# voltage_level_translators_schematic.net
KiCad netlist of a schematic drawn in Altium Designer
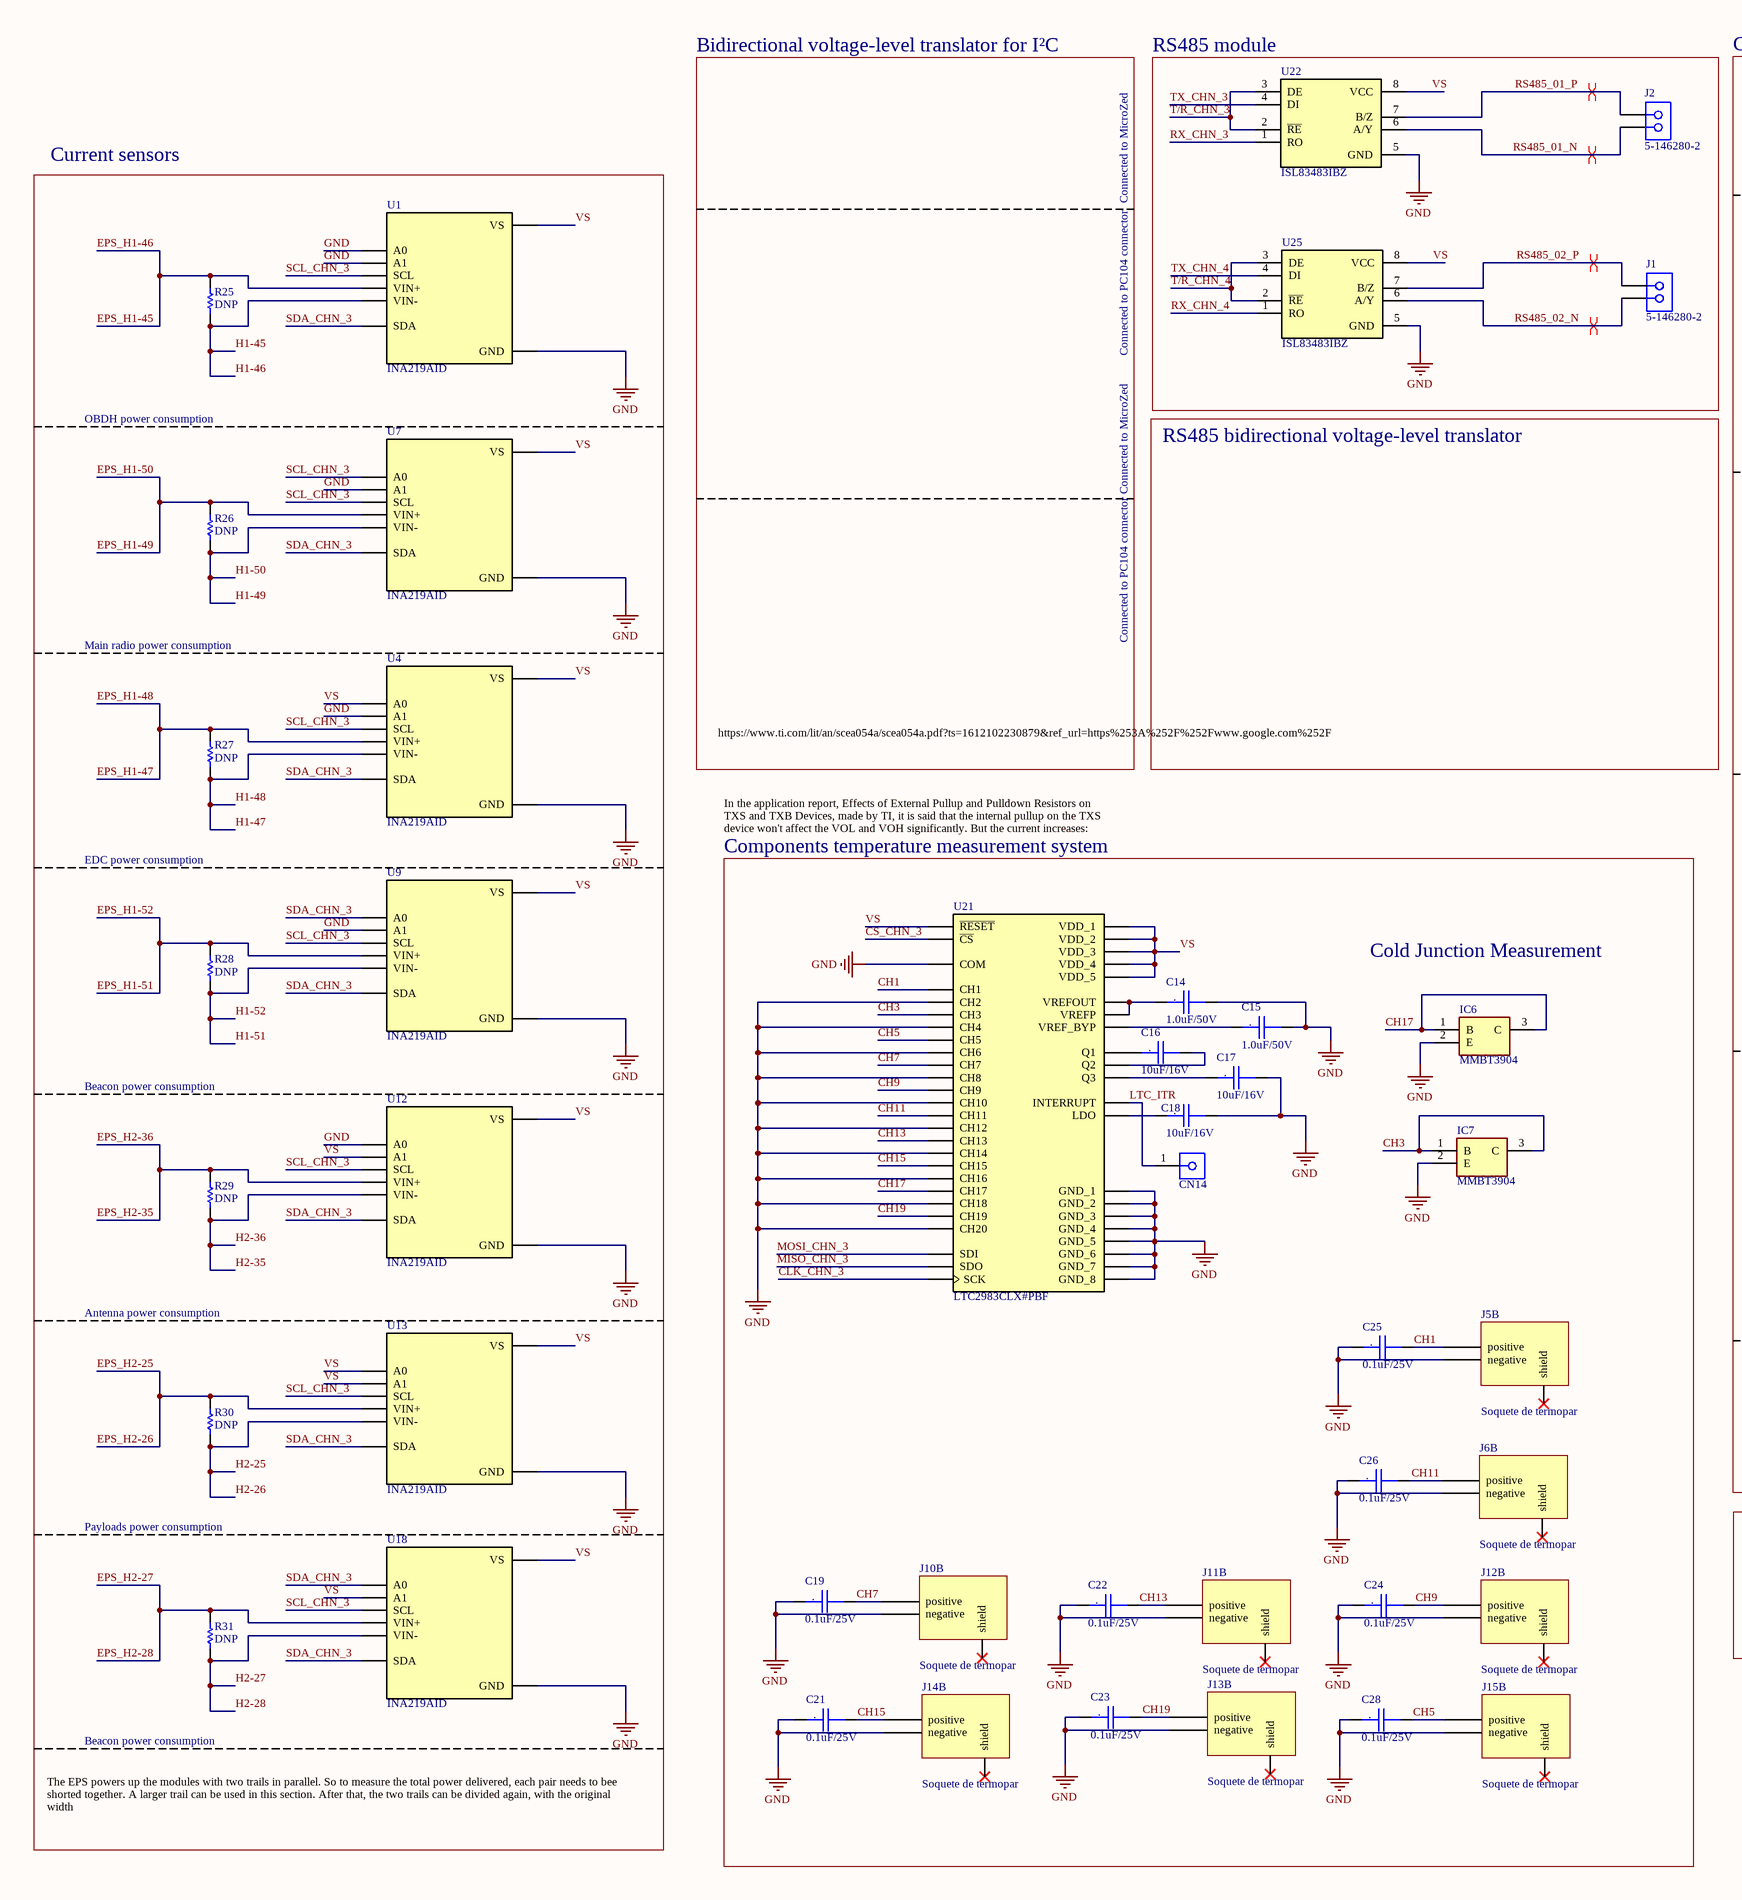
[diagram p0: voltage_level_translators_schematic.SchDoc, left]
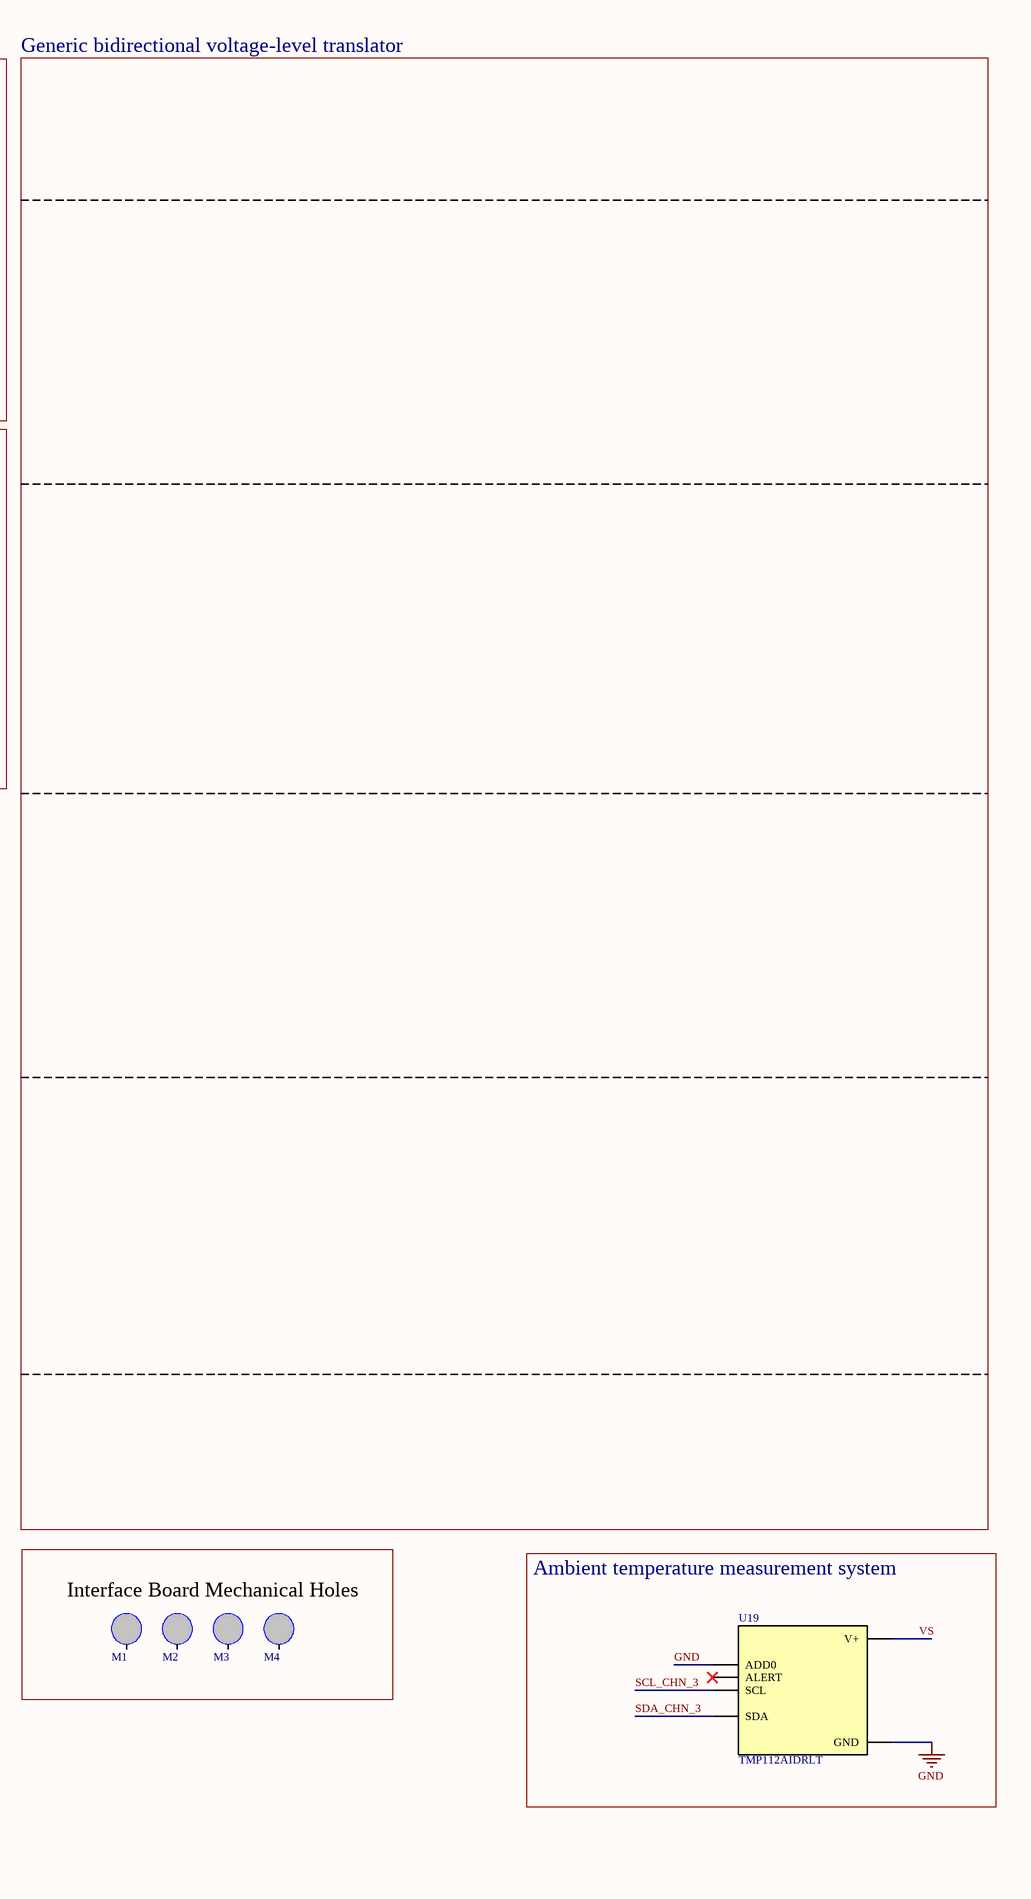
[diagram p1: voltage_level_translators_schematic.SchDoc, right]

(export (version "E")
  (design (tool "Eeschema 10.0.6"))
  (components
    (comp (ref "C14")
      (value "1.0uF/50V")
      (footprint "CC0805")
      (description "CAP CER 1.0uF 50V 10% X7R 0805")
      (fields (field (name "MANUFACTURER PART NUMBER") "C0805X105K5RACAUTO"))
      (libsource (lib "flatsat_platform_2") (part "Cap_Cer_X7R_1.0uF_50V_0805"))
    )
    (comp (ref "C15")
      (value "1.0uF/50V")
      (footprint "CC0805")
      (description "CAP CER 1.0uF 50V 10% X7R 0805")
      (fields (field (name "MANUFACTURER PART NUMBER") "C0805X105K5RACAUTO"))
      (libsource (lib "flatsat_platform_2") (part "Cap_Cer_X7R_1.0uF_50V_0805"))
    )
    (comp (ref "C16")
      (value "10uF/16V")
      (footprint "CC1210")
      (description "CAP CER 10uF 16V 10% X7R 1210")
      (fields (field (name "MANUFACTURER PART NUMBER") "C1210C106K4RACTU"))
      (libsource (lib "flatsat_platform_2") (part "Cap_Cer_X7R_10uF_16V_1210"))
    )
    (comp (ref "C17")
      (value "10uF/16V")
      (footprint "CC1210")
      (description "CAP CER 10uF 16V 10% X7R 1210")
      (fields (field (name "MANUFACTURER PART NUMBER") "C1210C106K4RACTU"))
      (libsource (lib "flatsat_platform_2") (part "Cap_Cer_X7R_10uF_16V_1210"))
    )
    (comp (ref "C18")
      (value "10uF/16V")
      (footprint "CC1210")
      (description "CAP CER 10uF 16V 10% X7R 1210")
      (fields (field (name "MANUFACTURER PART NUMBER") "C1210C106K4RACTU"))
      (libsource (lib "flatsat_platform_2") (part "Cap_Cer_X7R_10uF_16V_1210"))
    )
    (comp (ref "C19")
      (value "0.1uF/25V")
      (footprint "CC0805")
      (description "CAP CER 0.1uF 25V 10% X7R 0805")
      (fields (field (name "MANUFACTURER PART NUMBER") "CC0805KRX7R8BB104"))
      (libsource (lib "flatsat_platform_2") (part "Cap_Cer_X7R_0.1uF_25V_0805"))
    )
    (comp (ref "C21")
      (value "0.1uF/25V")
      (footprint "CC0805")
      (description "CAP CER 0.1uF 25V 10% X7R 0805")
      (fields (field (name "MANUFACTURER PART NUMBER") "CC0805KRX7R8BB104"))
      (libsource (lib "flatsat_platform_2") (part "Cap_Cer_X7R_0.1uF_25V_0805"))
    )
    (comp (ref "C22")
      (value "0.1uF/25V")
      (footprint "CC0805")
      (description "CAP CER 0.1uF 25V 10% X7R 0805")
      (fields (field (name "MANUFACTURER PART NUMBER") "CC0805KRX7R8BB104"))
      (libsource (lib "flatsat_platform_2") (part "Cap_Cer_X7R_0.1uF_25V_0805"))
    )
    (comp (ref "C23")
      (value "0.1uF/25V")
      (footprint "CC0805")
      (description "CAP CER 0.1uF 25V 10% X7R 0805")
      (fields (field (name "MANUFACTURER PART NUMBER") "CC0805KRX7R8BB104"))
      (libsource (lib "flatsat_platform_2") (part "Cap_Cer_X7R_0.1uF_25V_0805"))
    )
    (comp (ref "C24")
      (value "0.1uF/25V")
      (footprint "CC0805")
      (description "CAP CER 0.1uF 25V 10% X7R 0805")
      (fields (field (name "MANUFACTURER PART NUMBER") "CC0805KRX7R8BB104"))
      (libsource (lib "flatsat_platform_2") (part "Cap_Cer_X7R_0.1uF_25V_0805"))
    )
    (comp (ref "C25")
      (value "0.1uF/25V")
      (footprint "CC0805")
      (description "CAP CER 0.1uF 25V 10% X7R 0805")
      (fields (field (name "MANUFACTURER PART NUMBER") "CC0805KRX7R8BB104"))
      (libsource (lib "flatsat_platform_2") (part "Cap_Cer_X7R_0.1uF_25V_0805"))
    )
    (comp (ref "C26")
      (value "0.1uF/25V")
      (footprint "CC0805")
      (description "CAP CER 0.1uF 25V 10% X7R 0805")
      (fields (field (name "MANUFACTURER PART NUMBER") "CC0805KRX7R8BB104"))
      (libsource (lib "flatsat_platform_2") (part "Cap_Cer_X7R_0.1uF_25V_0805"))
    )
    (comp (ref "C28")
      (value "0.1uF/25V")
      (footprint "CC0805")
      (description "CAP CER 0.1uF 25V 10% X7R 0805")
      (fields (field (name "MANUFACTURER PART NUMBER") "CC0805KRX7R8BB104"))
      (libsource (lib "flatsat_platform_2") (part "Cap_Cer_X7R_0.1uF_25V_0805"))
    )
    (comp (ref "CN14")
      (value "TSW-101-05-T-S")
      (footprint "PIN BAR 1 2.54mm 180 GRAUS - Hide")
      (description "CONN HEADER 1POS .100\" SNGL TIN")
      (fields (field (name "MANUFACTURER") "Samtec Inc"))
      (libsource (lib "flatsat_platform_2") (part "TSW-101-05-T-S"))
    )
    (comp (ref "IC6")
      (value "MMBT3904")
      (footprint "SamacSys:SOT95P240X120-3N")
      (description "Integrated Circuit")
      (fields (field (name "MOUSER PART NUMBER") "637-MMBT3904"))
      (libsource (lib "*") (part "MMBT3904"))
    )
    (comp (ref "IC7")
      (value "MMBT3904")
      (footprint "SamacSys:SOT95P240X120-3N")
      (description "Integrated Circuit")
      (fields (field (name "MOUSER PART NUMBER") "637-MMBT3904"))
      (libsource (lib "*") (part "MMBT3904"))
    )
    (comp (ref "J1")
      (value "5-146280-2")
      (footprint "PIN BAR 2 2.54mm 180 GRAUS")
      (description "02 MODII HDR SRST B/A .100CL")
      (fields (field (name "MF") "TE Connectivity"))
      (libsource (lib "flatsat_platform_2") (part "5-146280-2"))
    )
    (comp (ref "J2")
      (value "5-146280-2")
      (footprint "PIN BAR 2 2.54mm 180 GRAUS")
      (description "02 MODII HDR SRST B/A .100CL")
      (fields (field (name "MF") "TE Connectivity"))
      (libsource (lib "flatsat_platform_2") (part "5-146280-2"))
    )
    (comp (ref "J5")
      (value "Soquete de termopar")
      (footprint "PCC-SMP-V-K")
      (description "Soquete de termopar especial PCCS para placa de circuito em série")
      (libsource (lib "Thermocouple_connector") (part "PCC-SMP-V-K"))
    )
    (comp (ref "J6")
      (value "Soquete de termopar")
      (footprint "PCC-SMP-V-K")
      (description "Soquete de termopar especial PCCS para placa de circuito em série")
      (libsource (lib "Thermocouple_connector") (part "PCC-SMP-V-K"))
    )
    (comp (ref "J10")
      (value "Soquete de termopar")
      (footprint "PCC-SMP-V-K")
      (description "Soquete de termopar especial PCCS para placa de circuito em série")
      (libsource (lib "Thermocouple_connector") (part "PCC-SMP-V-K"))
    )
    (comp (ref "J11")
      (value "Soquete de termopar")
      (footprint "PCC-SMP-V-K")
      (description "Soquete de termopar especial PCCS para placa de circuito em série")
      (libsource (lib "Thermocouple_connector") (part "PCC-SMP-V-K"))
    )
    (comp (ref "J12")
      (value "Soquete de termopar")
      (footprint "PCC-SMP-V-K")
      (description "Soquete de termopar especial PCCS para placa de circuito em série")
      (libsource (lib "Thermocouple_connector") (part "PCC-SMP-V-K"))
    )
    (comp (ref "J13")
      (value "Soquete de termopar")
      (footprint "PCC-SMP-V-K")
      (description "Soquete de termopar especial PCCS para placa de circuito em série")
      (libsource (lib "Thermocouple_connector") (part "PCC-SMP-V-K"))
    )
    (comp (ref "J14")
      (value "Soquete de termopar")
      (footprint "PCC-SMP-V-K")
      (description "Soquete de termopar especial PCCS para placa de circuito em série")
      (libsource (lib "Thermocouple_connector") (part "PCC-SMP-V-K"))
    )
    (comp (ref "J15")
      (value "Soquete de termopar")
      (footprint "PCC-SMP-V-K")
      (description "Soquete de termopar especial PCCS para placa de circuito em série")
      (libsource (lib "Thermocouple_connector") (part "PCC-SMP-V-K"))
    )
    (comp (ref "M1")
      (value "IB Mechanical Hole")
      (footprint "M3 hole (5.5mm pad)")
      (description "Mechanical Hole for FloripaSat-2 interface boards")
      (libsource (lib "iip") (part "IB Mechanical Hole"))
    )
    (comp (ref "M2")
      (value "IB Mechanical Hole")
      (footprint "M3 hole (5.5mm pad)")
      (description "Mechanical Hole for FloripaSat-2 interface boards")
      (libsource (lib "iip") (part "IB Mechanical Hole"))
    )
    (comp (ref "M3")
      (value "IB Mechanical Hole")
      (footprint "M3 hole (5.5mm pad)")
      (description "Mechanical Hole for FloripaSat-2 interface boards")
      (libsource (lib "iip") (part "IB Mechanical Hole"))
    )
    (comp (ref "M4")
      (value "IB Mechanical Hole")
      (footprint "M3 hole (5.5mm pad)")
      (description "Mechanical Hole for FloripaSat-2 interface boards")
      (libsource (lib "iip") (part "IB Mechanical Hole"))
    )
    (comp (ref "R25")
      (value "DNP")
      (footprint "0805")
      (description "RES DNP 0805")
      (fields (field (name "MANUFACTURER PART NUMBER") "UR73V2ATTD47L0F"))
      (libsource (lib "flatsat_platform_2") (part "RDNP_0805"))
    )
    (comp (ref "R26")
      (value "DNP")
      (footprint "0805")
      (description "RES DNP 0805")
      (fields (field (name "MANUFACTURER PART NUMBER") "UR73V2ATTD47L0F"))
      (libsource (lib "flatsat_platform_2") (part "RDNP_0805"))
    )
    (comp (ref "R27")
      (value "DNP")
      (footprint "0805")
      (description "RES DNP 0805")
      (fields (field (name "MANUFACTURER PART NUMBER") "UR73V2ATTD47L0F"))
      (libsource (lib "flatsat_platform_2") (part "RDNP_0805"))
    )
    (comp (ref "R28")
      (value "DNP")
      (footprint "0805")
      (description "RES DNP 0805")
      (fields (field (name "MANUFACTURER PART NUMBER") "UR73V2ATTD47L0F"))
      (libsource (lib "flatsat_platform_2") (part "RDNP_0805"))
    )
    (comp (ref "R29")
      (value "DNP")
      (footprint "0805")
      (description "RES DNP 0805")
      (fields (field (name "MANUFACTURER PART NUMBER") "UR73V2ATTD47L0F"))
      (libsource (lib "flatsat_platform_2") (part "RDNP_0805"))
    )
    (comp (ref "R30")
      (value "DNP")
      (footprint "0805")
      (description "RES DNP 0805")
      (fields (field (name "MANUFACTURER PART NUMBER") "UR73V2ATTD47L0F"))
      (libsource (lib "flatsat_platform_2") (part "RDNP_0805"))
    )
    (comp (ref "R31")
      (value "DNP")
      (footprint "0805")
      (description "RES DNP 0805")
      (fields (field (name "MANUFACTURER PART NUMBER") "UR73V2ATTD47L0F"))
      (libsource (lib "flatsat_platform_2") (part "RDNP_0805"))
    )
    (comp (ref "U1")
      (value "INA219AID")
      (footprint "SOIC127P599X175-8N")
      (description "26V, 12-bit, i2c output current/voltage/power monitor 8-SOIC -40 to 125")
      (fields (field (name "MF") "Texas Instruments"))
      (libsource (lib "flatsat_platform_2") (part "INA219AID"))
    )
    (comp (ref "U4")
      (value "INA219AID")
      (footprint "SOIC127P599X175-8N")
      (description "26V, 12-bit, i2c output current/voltage/power monitor 8-SOIC -40 to 125")
      (fields (field (name "MF") "Texas Instruments"))
      (libsource (lib "flatsat_platform_2") (part "INA219AID"))
    )
    (comp (ref "U7")
      (value "INA219AID")
      (footprint "SOIC127P599X175-8N")
      (description "26V, 12-bit, i2c output current/voltage/power monitor 8-SOIC -40 to 125")
      (fields (field (name "MF") "Texas Instruments"))
      (libsource (lib "flatsat_platform_2") (part "INA219AID"))
    )
    (comp (ref "U9")
      (value "INA219AID")
      (footprint "SOIC127P599X175-8N")
      (description "26V, 12-bit, i2c output current/voltage/power monitor 8-SOIC -40 to 125")
      (fields (field (name "MF") "Texas Instruments"))
      (libsource (lib "flatsat_platform_2") (part "INA219AID"))
    )
    (comp (ref "U12")
      (value "INA219AID")
      (footprint "SOIC127P599X175-8N")
      (description "26V, 12-bit, i2c output current/voltage/power monitor 8-SOIC -40 to 125")
      (fields (field (name "MF") "Texas Instruments"))
      (libsource (lib "flatsat_platform_2") (part "INA219AID"))
    )
    (comp (ref "U13")
      (value "INA219AID")
      (footprint "SOIC127P599X175-8N")
      (description "26V, 12-bit, i2c output current/voltage/power monitor 8-SOIC -40 to 125")
      (fields (field (name "MF") "Texas Instruments"))
      (libsource (lib "flatsat_platform_2") (part "INA219AID"))
    )
    (comp (ref "U18")
      (value "INA219AID")
      (footprint "SOIC127P599X175-8N")
      (description "26V, 12-bit, i2c output current/voltage/power monitor 8-SOIC -40 to 125")
      (fields (field (name "MF") "Texas Instruments"))
      (libsource (lib "flatsat_platform_2") (part "INA219AID"))
    )
    (comp (ref "U19")
      (value "TMP112AIDRLT")
      (footprint "SOT50P160X60-6N")
      (fields (field (name "MF") "Texas Instruments"))
      (libsource (lib "flatsat_platform_2") (part "TMP112AIDRLT"))
    )
    (comp (ref "U21")
      (value "LTC2983CLX#PBF")
      (footprint "QFP50P900X900X160-48N")
      (description "IC SENSOR THERMAL")
      (fields (field (name "MF") "Analog Devices"))
      (libsource (lib "flatsat_platform_2") (part "LTC2983CLX#PBF"))
    )
    (comp (ref "U22")
      (value "ISL83483IBZ")
      (footprint "SOIC127P600X175-8N")
      (description "1/1 Transceiver Half RS422, RS485 8-SOIC")
      (fields
        (field (name "MF") "Renesas Electronics")
        (field (name "MANUFACTURER PART NUMBER") "ISL83483IBZ-T")
      )
      (libsource (lib "flatsat_platform_2") (part "ISL83483IBZ"))
    )
    (comp (ref "U25")
      (value "ISL83483IBZ")
      (footprint "SOIC127P600X175-8N")
      (description "1/1 Transceiver Half RS422, RS485 8-SOIC")
      (fields
        (field (name "MF") "Renesas Electronics")
        (field (name "MANUFACTURER PART NUMBER") "ISL83483IBZ-T")
      )
      (libsource (lib "flatsat_platform_2") (part "ISL83483IBZ"))
    )
  )
  (nets
    (net (code "1") (name "/CH1") (class "Default")
      (node (ref "C25") (pin "2") (pinfunction "2_2") (pintype "passive"))
      (node (ref "J5") (pin "2") (pinfunction "positive_2") (pintype "passive"))
      (node (ref "U21") (pin "16") (pinfunction "CH1_16") (pintype "power_in"))
    )
    (net (code "2") (name "/CH3") (class "Default")
      (node (ref "IC7") (pin "1") (pinfunction "B_1") (pintype "passive"))
      (node (ref "IC7") (pin "3") (pinfunction "C_3") (pintype "passive"))
      (node (ref "U21") (pin "18") (pinfunction "CH3_18") (pintype "power_in"))
    )
    (net (code "3") (name "/CH5") (class "Default")
      (node (ref "C28") (pin "2") (pinfunction "2_2") (pintype "passive"))
      (node (ref "J15") (pin "2") (pinfunction "positive_2") (pintype "passive"))
      (node (ref "U21") (pin "20") (pinfunction "CH5_20") (pintype "power_in"))
    )
    (net (code "4") (name "/CH7") (class "Default")
      (node (ref "C19") (pin "2") (pinfunction "2_2") (pintype "passive"))
      (node (ref "J10") (pin "2") (pinfunction "positive_2") (pintype "passive"))
      (node (ref "U21") (pin "22") (pinfunction "CH7_22") (pintype "power_in"))
    )
    (net (code "5") (name "/CH9") (class "Default")
      (node (ref "C24") (pin "2") (pinfunction "2_2") (pintype "passive"))
      (node (ref "J12") (pin "2") (pinfunction "positive_2") (pintype "passive"))
      (node (ref "U21") (pin "24") (pinfunction "CH9_24") (pintype "power_in"))
    )
    (net (code "6") (name "/CH11") (class "Default")
      (node (ref "C26") (pin "2") (pinfunction "2_2") (pintype "passive"))
      (node (ref "J6") (pin "2") (pinfunction "positive_2") (pintype "passive"))
      (node (ref "U21") (pin "26") (pinfunction "CH11_26") (pintype "power_in"))
    )
    (net (code "7") (name "/CH13") (class "Default")
      (node (ref "C22") (pin "2") (pinfunction "2_2") (pintype "passive"))
      (node (ref "J11") (pin "2") (pinfunction "positive_2") (pintype "passive"))
      (node (ref "U21") (pin "28") (pinfunction "CH13_28") (pintype "power_in"))
    )
    (net (code "8") (name "/CH15") (class "Default")
      (node (ref "C21") (pin "2") (pinfunction "2_2") (pintype "passive"))
      (node (ref "J14") (pin "2") (pinfunction "positive_2") (pintype "passive"))
      (node (ref "U21") (pin "30") (pinfunction "CH15_30") (pintype "power_in"))
    )
    (net (code "9") (name "/CH17") (class "Default")
      (node (ref "IC6") (pin "1") (pinfunction "B_1") (pintype "passive"))
      (node (ref "IC6") (pin "3") (pinfunction "C_3") (pintype "passive"))
      (node (ref "U21") (pin "32") (pinfunction "CH17_32") (pintype "power_in"))
    )
    (net (code "10") (name "/CH19") (class "Default")
      (node (ref "C23") (pin "2") (pinfunction "2_2") (pintype "passive"))
      (node (ref "J13") (pin "2") (pinfunction "positive_2") (pintype "passive"))
      (node (ref "U21") (pin "34") (pinfunction "CH19_34") (pintype "power_in"))
    )
    (net (code "11") (name "/CLK_CHN_3") (class "Default")
      (node (ref "U21") (pin "38") (pinfunction "SCK_38") (pintype "power_in"))
    )
    (net (code "12") (name "/CS_CHN_3") (class "Default")
      (node (ref "U21") (pin "41") (pinfunction "~{CS}_41") (pintype "power_in"))
    )
    (net (code "13") (name "/EPS_H1-45") (class "Default")
      (node (ref "R25") (pin "1") (pinfunction "1_1") (pintype "passive"))
      (node (ref "U1") (pin "8") (pinfunction "VIN+_8") (pintype "power_in"))
    )
    (net (code "14") (name "/EPS_H1-47") (class "Default")
      (node (ref "R27") (pin "1") (pinfunction "1_1") (pintype "passive"))
      (node (ref "U4") (pin "8") (pinfunction "VIN+_8") (pintype "power_in"))
    )
    (net (code "15") (name "/EPS_H1-49") (class "Default")
      (node (ref "R26") (pin "1") (pinfunction "1_1") (pintype "passive"))
      (node (ref "U7") (pin "8") (pinfunction "VIN+_8") (pintype "power_in"))
    )
    (net (code "16") (name "/EPS_H1-51") (class "Default")
      (node (ref "R28") (pin "1") (pinfunction "1_1") (pintype "passive"))
      (node (ref "U9") (pin "8") (pinfunction "VIN+_8") (pintype "power_in"))
    )
    (net (code "17") (name "/EPS_H2-25") (class "Default")
      (node (ref "R30") (pin "1") (pinfunction "1_1") (pintype "passive"))
      (node (ref "U13") (pin "8") (pinfunction "VIN+_8") (pintype "power_in"))
    )
    (net (code "18") (name "/EPS_H2-27") (class "Default")
      (node (ref "R31") (pin "1") (pinfunction "1_1") (pintype "passive"))
      (node (ref "U18") (pin "8") (pinfunction "VIN+_8") (pintype "power_in"))
    )
    (net (code "19") (name "/EPS_H2-35") (class "Default")
      (node (ref "R29") (pin "1") (pinfunction "1_1") (pintype "passive"))
      (node (ref "U12") (pin "8") (pinfunction "VIN+_8") (pintype "power_in"))
    )
    (net (code "20") (name "/H1-45") (class "Default")
      (node (ref "R25") (pin "2") (pinfunction "2_2") (pintype "passive"))
      (node (ref "U1") (pin "7") (pinfunction "VIN-_7") (pintype "power_in"))
    )
    (net (code "21") (name "/H1-47") (class "Default")
      (node (ref "R27") (pin "2") (pinfunction "2_2") (pintype "passive"))
      (node (ref "U4") (pin "7") (pinfunction "VIN-_7") (pintype "power_in"))
    )
    (net (code "22") (name "/H1-49") (class "Default")
      (node (ref "R26") (pin "2") (pinfunction "2_2") (pintype "passive"))
      (node (ref "U7") (pin "7") (pinfunction "VIN-_7") (pintype "power_in"))
    )
    (net (code "23") (name "/H1-51") (class "Default")
      (node (ref "R28") (pin "2") (pinfunction "2_2") (pintype "passive"))
      (node (ref "U9") (pin "7") (pinfunction "VIN-_7") (pintype "power_in"))
    )
    (net (code "24") (name "/H2-25") (class "Default")
      (node (ref "R30") (pin "2") (pinfunction "2_2") (pintype "passive"))
      (node (ref "U13") (pin "7") (pinfunction "VIN-_7") (pintype "power_in"))
    )
    (net (code "25") (name "/H2-27") (class "Default")
      (node (ref "R31") (pin "2") (pinfunction "2_2") (pintype "passive"))
      (node (ref "U18") (pin "7") (pinfunction "VIN-_7") (pintype "power_in"))
    )
    (net (code "26") (name "/H2-35") (class "Default")
      (node (ref "R29") (pin "2") (pinfunction "2_2") (pintype "passive"))
      (node (ref "U12") (pin "7") (pinfunction "VIN-_7") (pintype "power_in"))
    )
    (net (code "27") (name "/LTC_ITR") (class "Default")
      (node (ref "CN14") (pin "1") (pinfunction "1_1") (pintype "passive"))
      (node (ref "U21") (pin "37") (pinfunction "INTERRUPT_37") (pintype "power_in"))
    )
    (net (code "28") (name "/MISO_CHN_3") (class "Default")
      (node (ref "U21") (pin "39") (pinfunction "SDO_39") (pintype "power_in"))
    )
    (net (code "29") (name "/MOSI_CHN_3") (class "Default")
      (node (ref "U21") (pin "40") (pinfunction "SDI_40") (pintype "power_in"))
    )
    (net (code "30") (name "/RS485_01_N") (class "Default")
      (node (ref "J2") (pin "2") (pinfunction "2_2") (pintype "passive"))
      (node (ref "U22") (pin "6") (pinfunction "A/Y_6") (pintype "power_in"))
    )
    (net (code "31") (name "/RS485_01_P") (class "Default")
      (node (ref "J2") (pin "1") (pinfunction "1_1") (pintype "passive"))
      (node (ref "U22") (pin "7") (pinfunction "B/Z_7") (pintype "power_in"))
    )
    (net (code "32") (name "/RS485_02_N") (class "Default")
      (node (ref "J1") (pin "2") (pinfunction "2_2") (pintype "passive"))
      (node (ref "U25") (pin "6") (pinfunction "A/Y_6") (pintype "power_in"))
    )
    (net (code "33") (name "/RS485_02_P") (class "Default")
      (node (ref "J1") (pin "1") (pinfunction "1_1") (pintype "passive"))
      (node (ref "U25") (pin "7") (pinfunction "B/Z_7") (pintype "power_in"))
    )
    (net (code "34") (name "/RX_CHN_3") (class "Default")
      (node (ref "U22") (pin "1") (pinfunction "RO_1") (pintype "power_in"))
    )
    (net (code "35") (name "/RX_CHN_4") (class "Default")
      (node (ref "U25") (pin "1") (pinfunction "RO_1") (pintype "power_in"))
    )
    (net (code "36") (name "/SCL_CHN_3") (class "Default")
      (node (ref "U1") (pin "4") (pinfunction "SCL_4") (pintype "power_in"))
      (node (ref "U12") (pin "4") (pinfunction "SCL_4") (pintype "power_in"))
      (node (ref "U13") (pin "4") (pinfunction "SCL_4") (pintype "power_in"))
      (node (ref "U18") (pin "4") (pinfunction "SCL_4") (pintype "power_in"))
      (node (ref "U19") (pin "1") (pinfunction "SCL_1") (pintype "power_in"))
      (node (ref "U4") (pin "4") (pinfunction "SCL_4") (pintype "power_in"))
      (node (ref "U7") (pin "2") (pinfunction "A0_2") (pintype "power_in"))
      (node (ref "U7") (pin "4") (pinfunction "SCL_4") (pintype "power_in"))
      (node (ref "U9") (pin "4") (pinfunction "SCL_4") (pintype "power_in"))
    )
    (net (code "37") (name "/SDA_CHN_3") (class "Default")
      (node (ref "U1") (pin "3") (pinfunction "SDA_3") (pintype "power_in"))
      (node (ref "U12") (pin "3") (pinfunction "SDA_3") (pintype "power_in"))
      (node (ref "U13") (pin "3") (pinfunction "SDA_3") (pintype "power_in"))
      (node (ref "U18") (pin "2") (pinfunction "A0_2") (pintype "power_in"))
      (node (ref "U18") (pin "3") (pinfunction "SDA_3") (pintype "power_in"))
      (node (ref "U19") (pin "6") (pinfunction "SDA_6") (pintype "power_in"))
      (node (ref "U4") (pin "3") (pinfunction "SDA_3") (pintype "power_in"))
      (node (ref "U7") (pin "3") (pinfunction "SDA_3") (pintype "power_in"))
      (node (ref "U9") (pin "2") (pinfunction "A0_2") (pintype "power_in"))
      (node (ref "U9") (pin "3") (pinfunction "SDA_3") (pintype "power_in"))
    )
    (net (code "38") (name "/TX_CHN_3") (class "Default")
      (node (ref "U22") (pin "4") (pinfunction "DI_4") (pintype "power_in"))
    )
    (net (code "39") (name "/TX_CHN_4") (class "Default")
      (node (ref "U25") (pin "4") (pinfunction "DI_4") (pintype "power_in"))
    )
    (net (code "40") (name "/T{slash}R_CHN_3") (class "Default")
      (node (ref "U22") (pin "2") (pinfunction "~{RE}_2") (pintype "power_in"))
      (node (ref "U22") (pin "3") (pinfunction "DE_3") (pintype "power_in"))
    )
    (net (code "41") (name "/T{slash}R_CHN_4") (class "Default")
      (node (ref "U25") (pin "2") (pinfunction "~{RE}_2") (pintype "power_in"))
      (node (ref "U25") (pin "3") (pinfunction "DE_3") (pintype "power_in"))
    )
    (net (code "42") (name "/VS") (class "Default")
      (node (ref "U1") (pin "5") (pinfunction "VS_5") (pintype "power_in"))
      (node (ref "U12") (pin "1") (pinfunction "A1_1") (pintype "power_in"))
      (node (ref "U12") (pin "5") (pinfunction "VS_5") (pintype "power_in"))
      (node (ref "U13") (pin "1") (pinfunction "A1_1") (pintype "power_in"))
      (node (ref "U13") (pin "2") (pinfunction "A0_2") (pintype "power_in"))
      (node (ref "U13") (pin "5") (pinfunction "VS_5") (pintype "power_in"))
      (node (ref "U18") (pin "1") (pinfunction "A1_1") (pintype "power_in"))
      (node (ref "U18") (pin "5") (pinfunction "VS_5") (pintype "power_in"))
      (node (ref "U19") (pin "5") (pinfunction "V+_5") (pintype "power_in"))
      (node (ref "U21") (pin "2") (pinfunction "VDD_1_2") (pintype "power_in"))
      (node (ref "U21") (pin "4") (pinfunction "VDD_2_4") (pintype "power_in"))
      (node (ref "U21") (pin "42") (pinfunction "~{RESET}_42") (pintype "power_in"))
      (node (ref "U21") (pin "45") (pinfunction "VDD_5_45") (pintype "power_in"))
      (node (ref "U21") (pin "6") (pinfunction "VDD_3_6") (pintype "power_in"))
      (node (ref "U21") (pin "8") (pinfunction "VDD_4_8") (pintype "power_in"))
      (node (ref "U22") (pin "8") (pinfunction "VCC_8") (pintype "power_in"))
      (node (ref "U25") (pin "8") (pinfunction "VCC_8") (pintype "power_in"))
      (node (ref "U4") (pin "2") (pinfunction "A0_2") (pintype "power_in"))
      (node (ref "U4") (pin "5") (pinfunction "VS_5") (pintype "power_in"))
      (node (ref "U7") (pin "5") (pinfunction "VS_5") (pintype "power_in"))
      (node (ref "U9") (pin "5") (pinfunction "VS_5") (pintype "power_in"))
    )
    (net (code "43") (name "GND") (class "Default")
      (node (ref "C14") (pin "2") (pinfunction "2_2") (pintype "passive"))
      (node (ref "C15") (pin "2") (pinfunction "2_2") (pintype "passive"))
      (node (ref "C17") (pin "2") (pinfunction "2_2") (pintype "passive"))
      (node (ref "C18") (pin "2") (pinfunction "2_2") (pintype "passive"))
      (node (ref "C19") (pin "1") (pinfunction "1_1") (pintype "passive"))
      (node (ref "C21") (pin "1") (pinfunction "1_1") (pintype "passive"))
      (node (ref "C22") (pin "1") (pinfunction "1_1") (pintype "passive"))
      (node (ref "C23") (pin "1") (pinfunction "1_1") (pintype "passive"))
      (node (ref "C24") (pin "1") (pinfunction "1_1") (pintype "passive"))
      (node (ref "C25") (pin "1") (pinfunction "1_1") (pintype "passive"))
      (node (ref "C26") (pin "1") (pinfunction "1_1") (pintype "passive"))
      (node (ref "C28") (pin "1") (pinfunction "1_1") (pintype "passive"))
      (node (ref "IC6") (pin "2") (pinfunction "E_2") (pintype "passive"))
      (node (ref "IC7") (pin "2") (pinfunction "E_2") (pintype "passive"))
      (node (ref "J10") (pin "1") (pinfunction "negative_1") (pintype "passive"))
      (node (ref "J11") (pin "1") (pinfunction "negative_1") (pintype "passive"))
      (node (ref "J12") (pin "1") (pinfunction "negative_1") (pintype "passive"))
      (node (ref "J13") (pin "1") (pinfunction "negative_1") (pintype "passive"))
      (node (ref "J14") (pin "1") (pinfunction "negative_1") (pintype "passive"))
      (node (ref "J15") (pin "1") (pinfunction "negative_1") (pintype "passive"))
      (node (ref "J5") (pin "1") (pinfunction "negative_1") (pintype "passive"))
      (node (ref "J6") (pin "1") (pinfunction "negative_1") (pintype "passive"))
      (node (ref "U1") (pin "1") (pinfunction "A1_1") (pintype "power_in"))
      (node (ref "U1") (pin "2") (pinfunction "A0_2") (pintype "power_in"))
      (node (ref "U1") (pin "6") (pinfunction "GND_6") (pintype "power_in"))
      (node (ref "U12") (pin "2") (pinfunction "A0_2") (pintype "power_in"))
      (node (ref "U12") (pin "6") (pinfunction "GND_6") (pintype "power_in"))
      (node (ref "U13") (pin "6") (pinfunction "GND_6") (pintype "power_in"))
      (node (ref "U18") (pin "6") (pinfunction "GND_6") (pintype "power_in"))
      (node (ref "U19") (pin "2") (pinfunction "GND_2") (pintype "power_in"))
      (node (ref "U19") (pin "4") (pinfunction "ADD0_4") (pintype "power_in"))
      (node (ref "U21") (pin "1") (pinfunction "GND_1_1") (pintype "power_in"))
      (node (ref "U21") (pin "12") (pinfunction "GND_6_12") (pintype "power_in"))
      (node (ref "U21") (pin "15") (pinfunction "GND_7_15") (pintype "power_in"))
      (node (ref "U21") (pin "17") (pinfunction "CH2_17") (pintype "power_in"))
      (node (ref "U21") (pin "19") (pinfunction "CH4_19") (pintype "power_in"))
      (node (ref "U21") (pin "21") (pinfunction "CH6_21") (pintype "power_in"))
      (node (ref "U21") (pin "23") (pinfunction "CH8_23") (pintype "power_in"))
      (node (ref "U21") (pin "25") (pinfunction "CH10_25") (pintype "power_in"))
      (node (ref "U21") (pin "27") (pinfunction "CH12_27") (pintype "power_in"))
      (node (ref "U21") (pin "29") (pinfunction "CH14_29") (pintype "power_in"))
      (node (ref "U21") (pin "3") (pinfunction "GND_2_3") (pintype "power_in"))
      (node (ref "U21") (pin "31") (pinfunction "CH16_31") (pintype "power_in"))
      (node (ref "U21") (pin "33") (pinfunction "CH18_33") (pintype "power_in"))
      (node (ref "U21") (pin "35") (pinfunction "CH20_35") (pintype "power_in"))
      (node (ref "U21") (pin "36") (pinfunction "COM_36") (pintype "power_in"))
      (node (ref "U21") (pin "44") (pinfunction "GND_8_44") (pintype "power_in"))
      (node (ref "U21") (pin "5") (pinfunction "GND_3_5") (pintype "power_in"))
      (node (ref "U21") (pin "7") (pinfunction "GND_4_7") (pintype "power_in"))
      (node (ref "U21") (pin "9") (pinfunction "GND_5_9") (pintype "power_in"))
      (node (ref "U22") (pin "5") (pinfunction "GND_5") (pintype "power_in"))
      (node (ref "U25") (pin "5") (pinfunction "GND_5") (pintype "power_in"))
      (node (ref "U4") (pin "1") (pinfunction "A1_1") (pintype "power_in"))
      (node (ref "U4") (pin "6") (pinfunction "GND_6") (pintype "power_in"))
      (node (ref "U7") (pin "1") (pinfunction "A1_1") (pintype "power_in"))
      (node (ref "U7") (pin "6") (pinfunction "GND_6") (pintype "power_in"))
      (node (ref "U9") (pin "1") (pinfunction "A1_1") (pintype "power_in"))
      (node (ref "U9") (pin "6") (pinfunction "GND_6") (pintype "power_in"))
    )
    (net (code "44") (name "Net-(U21-LDO)") (class "Default")
      (node (ref "C18") (pin "1") (pinfunction "1_1") (pintype "passive"))
      (node (ref "U21") (pin "43") (pinfunction "LDO_43") (pintype "power_in"))
    )
    (net (code "45") (name "Net-(U21-Q1)") (class "Default")
      (node (ref "C16") (pin "1") (pinfunction "1_1") (pintype "passive"))
      (node (ref "U21") (pin "48") (pinfunction "Q1_48") (pintype "power_in"))
    )
    (net (code "46") (name "Net-(U21-Q2)") (class "Default")
      (node (ref "C16") (pin "2") (pinfunction "2_2") (pintype "passive"))
      (node (ref "U21") (pin "47") (pinfunction "Q2_47") (pintype "power_in"))
    )
    (net (code "47") (name "Net-(U21-Q3)") (class "Default")
      (node (ref "C17") (pin "1") (pinfunction "1_1") (pintype "passive"))
      (node (ref "U21") (pin "46") (pinfunction "Q3_46") (pintype "power_in"))
    )
    (net (code "48") (name "Net-(U21-VREFOUT)") (class "Default")
      (node (ref "C14") (pin "1") (pinfunction "1_1") (pintype "passive"))
      (node (ref "U21") (pin "13") (pinfunction "VREFOUT_13") (pintype "power_in"))
      (node (ref "U21") (pin "14") (pinfunction "VREFP_14") (pintype "power_in"))
    )
    (net (code "49") (name "Net-(U21-VREF_BYP)") (class "Default")
      (node (ref "C15") (pin "1") (pinfunction "1_1") (pintype "passive"))
      (node (ref "U21") (pin "11") (pinfunction "VREF_BYP_11") (pintype "power_in"))
    )
    (net (code "50") (name "unconnected-(J5B-shield-Pad3)") (class "Default")
      (node (ref "J5") (pin "3") (pinfunction "shield_3") (pintype "passive+no_connect"))
    )
    (net (code "51") (name "unconnected-(J6B-shield-Pad3)") (class "Default")
      (node (ref "J6") (pin "3") (pinfunction "shield_3") (pintype "passive+no_connect"))
    )
    (net (code "52") (name "unconnected-(J10B-shield-Pad3)") (class "Default")
      (node (ref "J10") (pin "3") (pinfunction "shield_3") (pintype "passive+no_connect"))
    )
    (net (code "53") (name "unconnected-(J11B-shield-Pad3)") (class "Default")
      (node (ref "J11") (pin "3") (pinfunction "shield_3") (pintype "passive+no_connect"))
    )
    (net (code "54") (name "unconnected-(J12B-shield-Pad3)") (class "Default")
      (node (ref "J12") (pin "3") (pinfunction "shield_3") (pintype "passive+no_connect"))
    )
    (net (code "55") (name "unconnected-(J13B-shield-Pad3)") (class "Default")
      (node (ref "J13") (pin "3") (pinfunction "shield_3") (pintype "passive+no_connect"))
    )
    (net (code "56") (name "unconnected-(J14B-shield-Pad3)") (class "Default")
      (node (ref "J14") (pin "3") (pinfunction "shield_3") (pintype "passive+no_connect"))
    )
    (net (code "57") (name "unconnected-(J15B-shield-Pad3)") (class "Default")
      (node (ref "J15") (pin "3") (pinfunction "shield_3") (pintype "passive+no_connect"))
    )
    (net (code "58") (name "unconnected-(M1-Pad0)") (class "Default")
      (node (ref "M1") (pin "0") (pinfunction "0_0") (pintype "passive"))
    )
    (net (code "59") (name "unconnected-(M2-Pad0)") (class "Default")
      (node (ref "M2") (pin "0") (pinfunction "0_0") (pintype "passive"))
    )
    (net (code "60") (name "unconnected-(M3-Pad0)") (class "Default")
      (node (ref "M3") (pin "0") (pinfunction "0_0") (pintype "passive"))
    )
    (net (code "61") (name "unconnected-(M4-Pad0)") (class "Default")
      (node (ref "M4") (pin "0") (pinfunction "0_0") (pintype "passive"))
    )
    (net (code "62") (name "unconnected-(U19-ALERT-Pad3)") (class "Default")
      (node (ref "U19") (pin "3") (pinfunction "ALERT_3") (pintype "power_in+no_connect"))
    )
  )
)
